# USB-C_-_UART_Serial_Bridge.net
KiCad netlist of a schematic drawn in Altium Designer
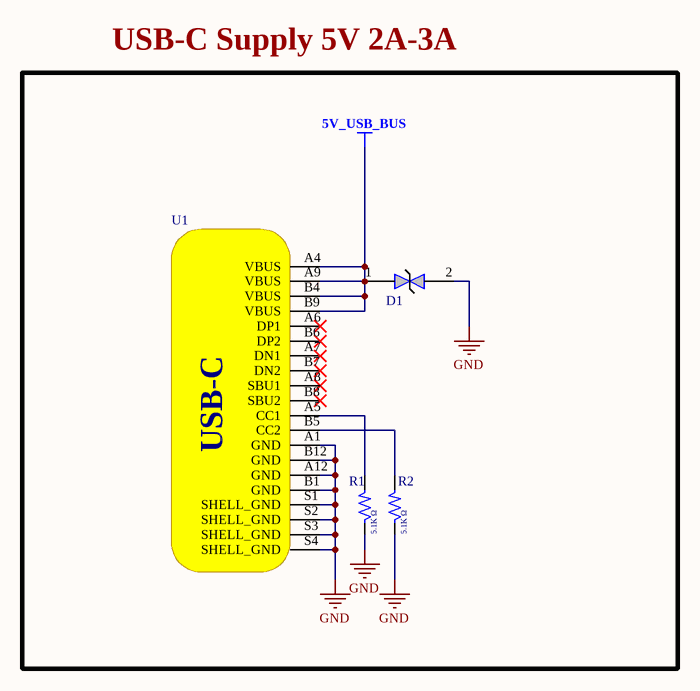
[diagram p0: USB-C - UART Serial Bridge.SchDoc]

(export (version "E")
  (design (tool "Eeschema 10.0.6"))
  (components
    (comp (ref "D1")
      (value "PESD3V3L1BA,")
      (footprint "Nexperia_SOD323_0")
      (libsource (lib "Mahdi-Library") (part "DIO_TVS_PESD3V3L1BA,115"))
    )
    (comp (ref "R1")
      (value "5.1K Ω")
      (footprint "RES_0603")
      (description "82 kOhms ±1% 0.125W, 1/8W Chip Resistor 0603 (1608 Metric) Anti-Sulfur Thin Film")
      (fields
        (field (name "MANUFACTURER") "Vishay Beyschlag")
        (field (name "MANUFACTURER PART NUMBER") "MCT06030C8202FP500")
      )
      (libsource (lib "NOUMANPCBLIB") (part "RES_82K-0.1W-1%-0603"))
    )
    (comp (ref "R2")
      (value "5.1K Ω")
      (footprint "RES_0603")
      (description "82 kOhms ±1% 0.125W, 1/8W Chip Resistor 0603 (1608 Metric) Anti-Sulfur Thin Film")
      (fields
        (field (name "MANUFACTURER") "Vishay Beyschlag")
        (field (name "MANUFACTURER PART NUMBER") "MCT06030C8202FP500")
      )
      (libsource (lib "NOUMANPCBLIB") (part "RES_82K-0.1W-1%-0603"))
    )
    (comp (ref "U1")
      (value "C393939")
      (footprint "USB-C 16Pin")
      (description "USB-C (USB TYPE-C) Receptacle Connector 16 Position Surface Mount, Right Angle")
      (fields (field (name "MANUFACTURER") "SHOU HAN"))
      (libsource (lib "Mahdi-SchLib") (part "USB-C 16Pin"))
    )
  )
  (nets
    (net (code "1") (name "5V_USB_BUS") (class "Default")
      (node (ref "D1") (pin "1") (pinfunction "1_1") (pintype "passive"))
      (node (ref "U1") (pin "A4") (pinfunction "VBUS_A4") (pintype "passive"))
      (node (ref "U1") (pin "A9") (pinfunction "VBUS_A9") (pintype "passive"))
      (node (ref "U1") (pin "B4") (pinfunction "VBUS_B4") (pintype "passive"))
      (node (ref "U1") (pin "B9") (pinfunction "VBUS_B9") (pintype "passive"))
    )
    (net (code "2") (name "GND") (class "Default")
      (node (ref "D1") (pin "2") (pinfunction "2_2") (pintype "passive"))
      (node (ref "R1") (pin "1") (pinfunction "1_1") (pintype "passive"))
      (node (ref "R2") (pin "1") (pinfunction "1_1") (pintype "passive"))
      (node (ref "U1") (pin "A1") (pinfunction "GND_A1") (pintype "passive"))
      (node (ref "U1") (pin "A12") (pinfunction "GND_A12") (pintype "passive"))
      (node (ref "U1") (pin "B1") (pinfunction "GND_B1") (pintype "passive"))
      (node (ref "U1") (pin "B12") (pinfunction "GND_B12") (pintype "passive"))
      (node (ref "U1") (pin "S1") (pinfunction "SHELL_GND_S1") (pintype "passive"))
      (node (ref "U1") (pin "S2") (pinfunction "SHELL_GND_S2") (pintype "passive"))
      (node (ref "U1") (pin "S3") (pinfunction "SHELL_GND_S3") (pintype "passive"))
      (node (ref "U1") (pin "S4") (pinfunction "SHELL_GND_S4") (pintype "passive"))
    )
    (net (code "3") (name "Net-(U1-CC1)") (class "Default")
      (node (ref "R1") (pin "2") (pinfunction "2_2") (pintype "passive"))
      (node (ref "U1") (pin "A5") (pinfunction "CC1_A5") (pintype "passive"))
    )
    (net (code "4") (name "Net-(U1-CC2)") (class "Default")
      (node (ref "R2") (pin "2") (pinfunction "2_2") (pintype "passive"))
      (node (ref "U1") (pin "B5") (pinfunction "CC2_B5") (pintype "passive"))
    )
    (net (code "5") (name "unconnected-(U1-DN1-PadA7)") (class "Default")
      (node (ref "U1") (pin "A7") (pinfunction "DN1_A7") (pintype "passive+no_connect"))
    )
    (net (code "6") (name "unconnected-(U1-DN2-PadB7)") (class "Default")
      (node (ref "U1") (pin "B7") (pinfunction "DN2_B7") (pintype "passive+no_connect"))
    )
    (net (code "7") (name "unconnected-(U1-DP1-PadA6)") (class "Default")
      (node (ref "U1") (pin "A6") (pinfunction "DP1_A6") (pintype "passive+no_connect"))
    )
    (net (code "8") (name "unconnected-(U1-DP2-PadB6)") (class "Default")
      (node (ref "U1") (pin "B6") (pinfunction "DP2_B6") (pintype "passive+no_connect"))
    )
    (net (code "9") (name "unconnected-(U1-SBU1-PadA8)") (class "Default")
      (node (ref "U1") (pin "A8") (pinfunction "SBU1_A8") (pintype "passive+no_connect"))
    )
    (net (code "10") (name "unconnected-(U1-SBU2-PadB8)") (class "Default")
      (node (ref "U1") (pin "B8") (pinfunction "SBU2_B8") (pintype "passive+no_connect"))
    )
  )
)
